# 100046138_block_diagram.net
KiCad netlist of a schematic drawn in Altium Designer
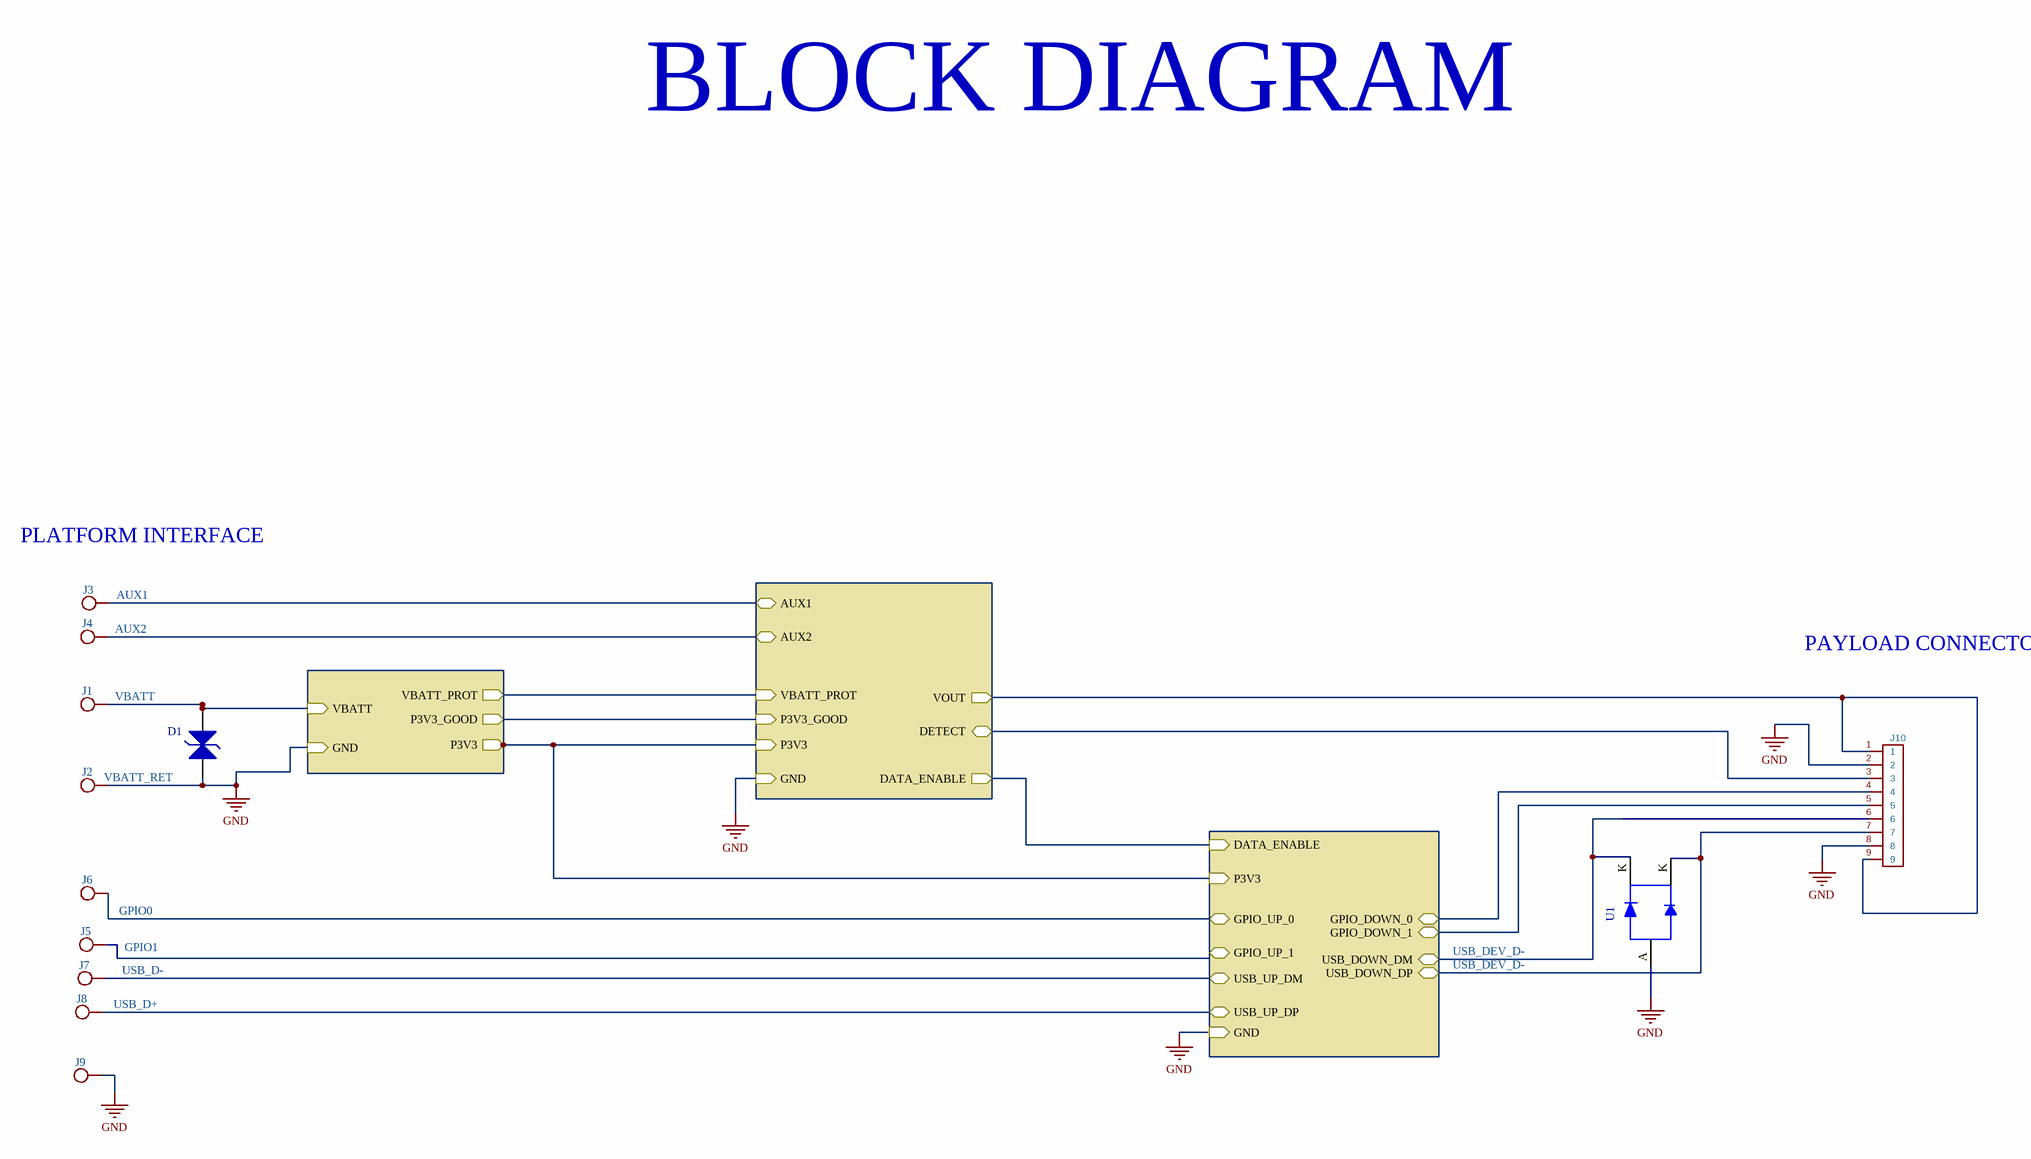
[diagram p0: 100046138_block_diagram.SchDoc]

(export (version "E")
  (design (tool "Eeschema 10.0.6"))
  (components
    (comp (ref "D1")
      (value "SMF26A")
      (footprint "DI-SOD123F-A")
      (description "SMF Series 200 W 26 V Uni-Directional Surface Mount TVS Diode - SOD-123F")
      (libsource (lib "Picatinny Server") (part "Diode - Bidirectional"))
    )
    (comp (ref "J1") (value "~") (footprint "PTH_18AWG") (libsource (lib "1a_Misc") (part "PTH_18AWG")))
    (comp (ref "J2") (value "~") (footprint "PTH_18AWG") (libsource (lib "1a_Misc") (part "PTH_18AWG")))
    (comp (ref "J3")
      (value "~")
      (footprint "PTH_24AWG_offset_rectangular")
      (libsource (lib "1a_Misc") (part "PTH_24AWG_offset_rectangle"))
    )
    (comp (ref "J4")
      (value "~")
      (footprint "PTH_24AWG_offset_rectangular")
      (libsource (lib "1a_Misc") (part "PTH_24AWG_offset_rectangle"))
    )
    (comp (ref "J5")
      (value "~")
      (footprint "PTH_24AWG_offset_rectangular")
      (libsource (lib "1a_Misc") (part "PTH_24AWG_offset_rectangle"))
    )
    (comp (ref "J6")
      (value "~")
      (footprint "PTH_24AWG_offset_rectangular")
      (libsource (lib "1a_Misc") (part "PTH_24AWG_offset_rectangle"))
    )
    (comp (ref "J7")
      (value "~")
      (footprint "PTH_24AWG_offset_rectangular")
      (libsource (lib "1a_Misc") (part "PTH_24AWG_offset_rectangle"))
    )
    (comp (ref "J8")
      (value "~")
      (footprint "PTH_24AWG_offset_rectangular")
      (libsource (lib "1a_Misc") (part "PTH_24AWG_offset_rectangle"))
    )
    (comp (ref "J9")
      (value "~")
      (footprint "PTH_24AWG_offset_rectangular")
      (libsource (lib "1a_Misc") (part "PTH_24AWG_offset_rectangle"))
    )
    (comp (ref "J10")
      (value "~")
      (footprint "399-10-109-10-007000")
      (fields
        (field (name "MANUFACTURER") "Mill-Max Manufacturing Corp.")
        (field (name "MPN") "399-10-109-10-007000")
      )
      (libsource (lib "1a_MillMax") (part "399-10-109-10-007000"))
    )
    (comp (ref "U1")
      (value "PESD5V0C2UM")
      (footprint "IC-SOT883-2-B")
      (description "Extremely low capacitance unidirectional ESD protection diode array")
      (libsource (lib "Picatinny Server") (part "Diode - TVS (Unidirectional)"))
    )
  )
  (nets
    (net (code "1") (name "/AUX1") (class "Default")
      (node (ref "J3") (pin "1") (pinfunction "1_1") (pintype "passive"))
    )
    (net (code "2") (name "/AUX2") (class "Default")
      (node (ref "J4") (pin "1") (pinfunction "1_1") (pintype "passive"))
    )
    (net (code "4") (name "/DETECT") (class "Default")
      (node (ref "J10") (pin "3") (pinfunction "3_3") (pintype "passive"))
    )
    (net (code "6") (name "/GPIO0") (class "Default")
      (node (ref "J6") (pin "1") (pinfunction "1_1") (pintype "passive"))
    )
    (net (code "8") (name "/GPIO_DOWN_0") (class "Default")
      (node (ref "J10") (pin "4") (pinfunction "4_4") (pintype "passive"))
    )
    (net (code "9") (name "/GPIO_DOWN_1") (class "Default")
      (node (ref "J10") (pin "5") (pinfunction "5_5") (pintype "passive"))
    )
    (net (code "13") (name "/USB_D+") (class "Default")
      (node (ref "J8") (pin "1") (pinfunction "1_1") (pintype "passive"))
    )
    (net (code "14") (name "/USB_D-") (class "Default")
      (node (ref "J7") (pin "1") (pinfunction "1_1") (pintype "passive"))
    )
    (net (code "15") (name "/USB_DEV_D-") (class "Default")
      (node (ref "J10") (pin "6") (pinfunction "6_6") (pintype "passive"))
      (node (ref "J10") (pin "7") (pinfunction "7_7") (pintype "passive"))
      (node (ref "U1") (pin "K") (pinfunction "K_K") (pintype "passive"))
    )
    (net (code "16") (name "/VBATT") (class "Default")
      (node (ref "D1") (pin "K") (pinfunction "K_K") (pintype "passive"))
      (node (ref "J1") (pin "1") (pinfunction "1_1") (pintype "passive"))
    )
    (net (code "19") (name "/VOUT") (class "Default")
      (node (ref "J10") (pin "1") (pinfunction "1_1") (pintype "passive"))
      (node (ref "J10") (pin "9") (pinfunction "9_9") (pintype "passive"))
    )
    (net (code "20") (name "GND") (class "Default")
      (node (ref "D1") (pin "A") (pinfunction "A_A") (pintype "passive"))
      (node (ref "J10") (pin "2") (pinfunction "2_2") (pintype "passive"))
      (node (ref "J10") (pin "8") (pinfunction "8_8") (pintype "passive"))
      (node (ref "J2") (pin "1") (pinfunction "1_1") (pintype "passive"))
      (node (ref "J9") (pin "1") (pinfunction "1_1") (pintype "passive"))
      (node (ref "U1") (pin "A") (pinfunction "A_A") (pintype "passive"))
    )
    (net (code "21") (name "unconnected-(J5-Pad1)") (class "Default")
      (node (ref "J5") (pin "1") (pinfunction "1_1") (pintype "passive"))
    )
  )
)
